# LPDDR2_16bits.net
KiCad netlist of a schematic drawn in Altium Designer
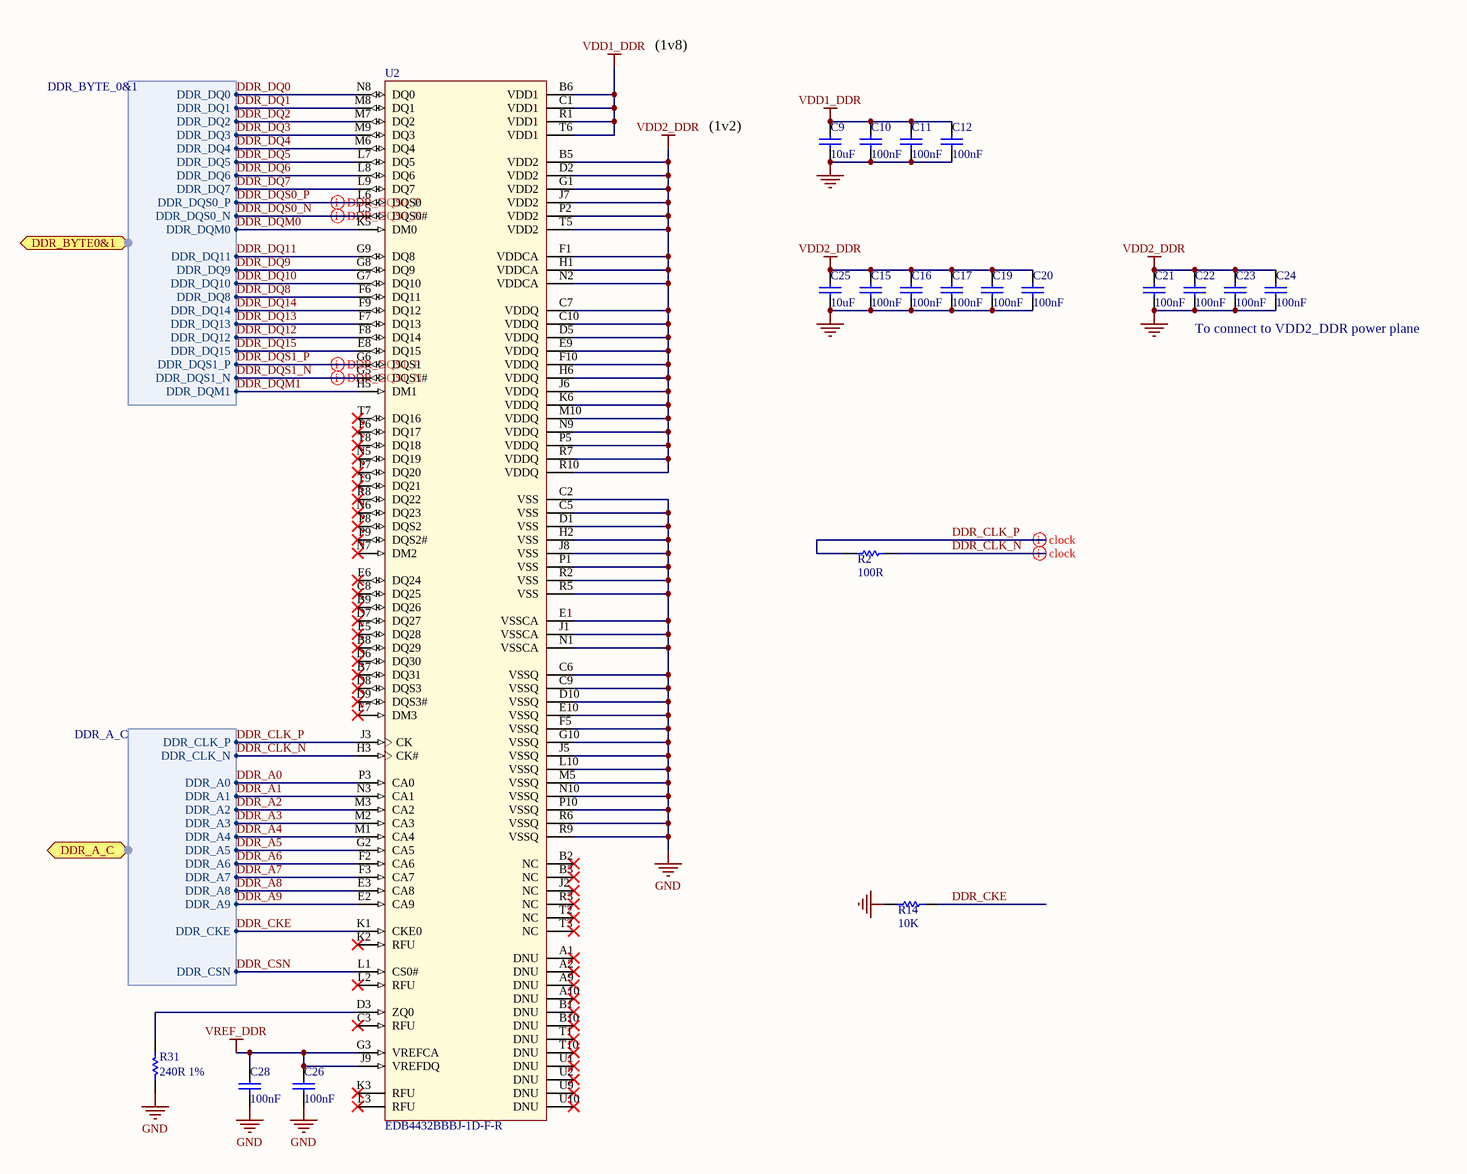
[diagram p0: LPDDR2_16bits .SchDoc]

(export (version "E")
  (design (tool "Eeschema 10.0.6"))
  (components
    (comp (ref "C9")
      (value "10uF")
      (footprint "C0603")
      (description "Capacitor, MLCC, 10uF, 10V, X5R, 10%, 0603, T=0.8mm")
      (fields
        (field (name "INTERNAL_PART_NUMBER") "MCD-01124")
        (field (name "MANUFACTURER_PART_NUMBER") "GRM188R61A106KAAL")
        (field (name "PROVIDED_BY") "SUBCO")
      )
      (libsource (lib "MCD_PARTS_database") (part "Capacitor"))
    )
    (comp (ref "C10")
      (value "100nF")
      (footprint "C0402")
      (description "Capacitor, MLCC, 100nF, 16V, X7R, 10%, 0402, T=0.5mm")
      (fields
        (field (name "INTERNAL_PART_NUMBER") "MCD-00006")
        (field (name "MANUFACTURER_PART_NUMBER") "CC0402KRX7R7BB104")
        (field (name "PROVIDED_BY") "SUBCO")
      )
      (libsource (lib "MCD_PARTS_database") (part "Capacitor"))
    )
    (comp (ref "C11")
      (value "100nF")
      (footprint "C0402")
      (description "Capacitor, MLCC, 100nF, 16V, X7R, 10%, 0402, T=0.5mm")
      (fields
        (field (name "INTERNAL_PART_NUMBER") "MCD-00006")
        (field (name "MANUFACTURER_PART_NUMBER") "CC0402KRX7R7BB104")
        (field (name "PROVIDED_BY") "SUBCO")
      )
      (libsource (lib "MCD_PARTS_database") (part "Capacitor"))
    )
    (comp (ref "C12")
      (value "100nF")
      (footprint "C0402")
      (description "Capacitor, MLCC, 100nF, 16V, X7R, 10%, 0402, T=0.5mm")
      (fields
        (field (name "INTERNAL_PART_NUMBER") "MCD-00006")
        (field (name "MANUFACTURER_PART_NUMBER") "CC0402KRX7R7BB104")
        (field (name "PROVIDED_BY") "SUBCO")
      )
      (libsource (lib "MCD_PARTS_database") (part "Capacitor"))
    )
    (comp (ref "C15")
      (value "100nF")
      (footprint "C0402")
      (description "Capacitor, MLCC, 100nF, 16V, X7R, 10%, 0402, T=0.5mm")
      (fields
        (field (name "INTERNAL_PART_NUMBER") "MCD-00006")
        (field (name "MANUFACTURER_PART_NUMBER") "CC0402KRX7R7BB104")
        (field (name "PROVIDED_BY") "SUBCO")
      )
      (libsource (lib "MCD_PARTS_database") (part "Capacitor"))
    )
    (comp (ref "C16")
      (value "100nF")
      (footprint "C0402")
      (description "Capacitor, MLCC, 100nF, 16V, X7R, 10%, 0402, T=0.5mm")
      (fields
        (field (name "INTERNAL_PART_NUMBER") "MCD-00006")
        (field (name "MANUFACTURER_PART_NUMBER") "CC0402KRX7R7BB104")
        (field (name "PROVIDED_BY") "SUBCO")
      )
      (libsource (lib "MCD_PARTS_database") (part "Capacitor"))
    )
    (comp (ref "C17")
      (value "100nF")
      (footprint "C0402")
      (description "Capacitor, MLCC, 100nF, 16V, X7R, 10%, 0402, T=0.5mm")
      (fields
        (field (name "INTERNAL_PART_NUMBER") "MCD-00006")
        (field (name "MANUFACTURER_PART_NUMBER") "CC0402KRX7R7BB104")
        (field (name "PROVIDED_BY") "SUBCO")
      )
      (libsource (lib "MCD_PARTS_database") (part "Capacitor"))
    )
    (comp (ref "C19")
      (value "100nF")
      (footprint "C0402")
      (description "Capacitor, MLCC, 100nF, 16V, X7R, 10%, 0402, T=0.5mm")
      (fields
        (field (name "INTERNAL_PART_NUMBER") "MCD-00006")
        (field (name "MANUFACTURER_PART_NUMBER") "CC0402KRX7R7BB104")
        (field (name "PROVIDED_BY") "SUBCO")
      )
      (libsource (lib "MCD_PARTS_database") (part "Capacitor"))
    )
    (comp (ref "C20")
      (value "100nF")
      (footprint "C0402")
      (description "Capacitor, MLCC, 100nF, 16V, X7R, 10%, 0402, T=0.5mm")
      (fields
        (field (name "INTERNAL_PART_NUMBER") "MCD-00006")
        (field (name "MANUFACTURER_PART_NUMBER") "CC0402KRX7R7BB104")
        (field (name "PROVIDED_BY") "SUBCO")
      )
      (libsource (lib "MCD_PARTS_database") (part "Capacitor"))
    )
    (comp (ref "C21")
      (value "100nF")
      (footprint "C0402")
      (description "Capacitor, MLCC, 100nF, 16V, X7R, 10%, 0402, T=0.5mm")
      (fields
        (field (name "INTERNAL_PART_NUMBER") "MCD-00006")
        (field (name "MANUFACTURER_PART_NUMBER") "CC0402KRX7R7BB104")
        (field (name "PROVIDED_BY") "SUBCO")
      )
      (libsource (lib "MCD_PARTS_database") (part "Capacitor"))
    )
    (comp (ref "C22")
      (value "100nF")
      (footprint "C0402")
      (description "Capacitor, MLCC, 100nF, 16V, X7R, 10%, 0402, T=0.5mm")
      (fields
        (field (name "INTERNAL_PART_NUMBER") "MCD-00006")
        (field (name "MANUFACTURER_PART_NUMBER") "CC0402KRX7R7BB104")
        (field (name "PROVIDED_BY") "SUBCO")
      )
      (libsource (lib "MCD_PARTS_database") (part "Capacitor"))
    )
    (comp (ref "C23")
      (value "100nF")
      (footprint "C0402")
      (description "Capacitor, MLCC, 100nF, 16V, X7R, 10%, 0402, T=0.5mm")
      (fields
        (field (name "INTERNAL_PART_NUMBER") "MCD-00006")
        (field (name "MANUFACTURER_PART_NUMBER") "CC0402KRX7R7BB104")
        (field (name "PROVIDED_BY") "SUBCO")
      )
      (libsource (lib "MCD_PARTS_database") (part "Capacitor"))
    )
    (comp (ref "C24")
      (value "100nF")
      (footprint "C0402")
      (description "Capacitor, MLCC, 100nF, 16V, X7R, 10%, 0402, T=0.5mm")
      (fields
        (field (name "INTERNAL_PART_NUMBER") "MCD-00006")
        (field (name "MANUFACTURER_PART_NUMBER") "CC0402KRX7R7BB104")
        (field (name "PROVIDED_BY") "SUBCO")
      )
      (libsource (lib "MCD_PARTS_database") (part "Capacitor"))
    )
    (comp (ref "C25")
      (value "10uF")
      (footprint "C0603")
      (description "Capacitor, MLCC, 10uF, 10V, X5R, 10%, 0603, T=0.8mm")
      (fields
        (field (name "INTERNAL_PART_NUMBER") "MCD-01124")
        (field (name "MANUFACTURER_PART_NUMBER") "GRM188R61A106KAAL")
        (field (name "PROVIDED_BY") "SUBCO")
      )
      (libsource (lib "MCD_PARTS_database") (part "Capacitor"))
    )
    (comp (ref "C26")
      (value "100nF")
      (footprint "C0402")
      (description "Capacitor, MLCC, 100nF, 16V, X7R, 10%, 0402, T=0.5mm")
      (fields
        (field (name "INTERNAL_PART_NUMBER") "MCD-00006")
        (field (name "MANUFACTURER_PART_NUMBER") "CC0402KRX7R7BB104")
        (field (name "PROVIDED_BY") "SUBCO")
      )
      (libsource (lib "MCD_PARTS_database") (part "Capacitor"))
    )
    (comp (ref "C28")
      (value "100nF")
      (footprint "C0402")
      (description "Capacitor, MLCC, 100nF, 16V, X7R, 10%, 0402, T=0.5mm")
      (fields
        (field (name "INTERNAL_PART_NUMBER") "MCD-00006")
        (field (name "MANUFACTURER_PART_NUMBER") "CC0402KRX7R7BB104")
        (field (name "PROVIDED_BY") "SUBCO")
      )
      (libsource (lib "MCD_PARTS_database") (part "Capacitor"))
    )
    (comp (ref "R2")
      (value "100R")
      (footprint "R0402")
      (description "Resistor,100R,0402,1%,1/16W")
      (fields
        (field (name "INTERNAL_PART_NUMBER") "MCD-00067")
        (field (name "MANUFACTURER_PART_NUMBER") "RC0402FR-07100RL")
        (field (name "PROVIDED_BY") "SUBCO")
      )
      (libsource (lib "MCD_PARTS_database") (part "Resistor"))
    )
    (comp (ref "R14")
      (value "10K")
      (footprint "R0402")
      (description "Resistor,10K,0402,1%,1/16W")
      (fields
        (field (name "INTERNAL_PART_NUMBER") "MCD-00053")
        (field (name "MANUFACTURER_PART_NUMBER") "RC0402FR-0710KL")
        (field (name "PROVIDED_BY") "SUBCO")
      )
      (libsource (lib "MCD_PARTS_database") (part "Resistor"))
    )
    (comp (ref "R31")
      (value "240R 1%")
      (footprint "R0402")
      (description "Resistor,240R,0402,1%,1/16W")
      (fields
        (field (name "INTERNAL_PART_NUMBER") "MCD-00120")
        (field (name "MANUFACTURER_PART_NUMBER") "RC0402FR-07240RL")
        (field (name "PROVIDED_BY") "SUBCO")
      )
      (libsource (lib "MCD_PARTS_database") (part "Resistor"))
    )
    (comp (ref "U2")
      (value "EDB4432BBBJ-1D-F-R")
      (footprint "ICC_WFBGA134_SDP-SAC302_10X11P5_P065")
      (description "Memory,LPDDR2,4Gb,128Mbx32,533MHz,1066Mb/s,1V8/1V2,FBGA134")
      (fields
        (field (name "INTERNAL_PART_NUMBER") "MCD-01223")
        (field (name "MANUFACTURER") "MICRON")
        (field (name "PROVIDED_BY") "SUBCO")
      )
      (libsource (lib "MCD_PARTS_database") (part "EDB4432BBBJ-1D-F-R"))
    )
  )
  (nets
    (net (code "3") (name "/DDR_A0") (class "Default")
      (node (ref "U2") (pin "P3") (pinfunction "CA0_P3") (pintype "input"))
    )
    (net (code "4") (name "/DDR_A1") (class "Default")
      (node (ref "U2") (pin "N3") (pinfunction "CA1_N3") (pintype "input"))
    )
    (net (code "5") (name "/DDR_A2") (class "Default")
      (node (ref "U2") (pin "M3") (pinfunction "CA2_M3") (pintype "input"))
    )
    (net (code "6") (name "/DDR_A3") (class "Default")
      (node (ref "U2") (pin "M2") (pinfunction "CA3_M2") (pintype "input"))
    )
    (net (code "7") (name "/DDR_A4") (class "Default")
      (node (ref "U2") (pin "M1") (pinfunction "CA4_M1") (pintype "input"))
    )
    (net (code "8") (name "/DDR_A5") (class "Default")
      (node (ref "U2") (pin "G2") (pinfunction "CA5_G2") (pintype "input"))
    )
    (net (code "9") (name "/DDR_A6") (class "Default")
      (node (ref "U2") (pin "F2") (pinfunction "CA6_F2") (pintype "input"))
    )
    (net (code "10") (name "/DDR_A7") (class "Default")
      (node (ref "U2") (pin "F3") (pinfunction "CA7_F3") (pintype "input"))
    )
    (net (code "11") (name "/DDR_A8") (class "Default")
      (node (ref "U2") (pin "E3") (pinfunction "CA8_E3") (pintype "input"))
    )
    (net (code "12") (name "/DDR_A9") (class "Default")
      (node (ref "U2") (pin "E2") (pinfunction "CA9_E2") (pintype "input"))
    )
    (net (code "13") (name "/DDR_CKE") (class "Default")
      (node (ref "R14") (pin "2") (pinfunction "2_2") (pintype "passive"))
      (node (ref "U2") (pin "K1") (pinfunction "CKE0_K1") (pintype "input"))
    )
    (net (code "14") (name "/DDR_CLK_N") (class "Default")
      (node (ref "R2") (pin "2") (pinfunction "2_2") (pintype "passive"))
      (node (ref "U2") (pin "H3") (pinfunction "CK#_H3") (pintype "input"))
    )
    (net (code "15") (name "/DDR_CLK_P") (class "Default")
      (node (ref "R2") (pin "1") (pinfunction "1_1") (pintype "passive"))
      (node (ref "U2") (pin "J3") (pinfunction "CK_J3") (pintype "input"))
    )
    (net (code "16") (name "/DDR_CSN") (class "Default")
      (node (ref "U2") (pin "L1") (pinfunction "CS0#_L1") (pintype "input"))
    )
    (net (code "17") (name "/DDR_DQ0") (class "Default")
      (node (ref "U2") (pin "N8") (pinfunction "DQ0_N8") (pintype "bidirectional"))
    )
    (net (code "18") (name "/DDR_DQ1") (class "Default")
      (node (ref "U2") (pin "M8") (pinfunction "DQ1_M8") (pintype "bidirectional"))
    )
    (net (code "19") (name "/DDR_DQ2") (class "Default")
      (node (ref "U2") (pin "M7") (pinfunction "DQ2_M7") (pintype "bidirectional"))
    )
    (net (code "20") (name "/DDR_DQ3") (class "Default")
      (node (ref "U2") (pin "M9") (pinfunction "DQ3_M9") (pintype "bidirectional"))
    )
    (net (code "21") (name "/DDR_DQ4") (class "Default")
      (node (ref "U2") (pin "M6") (pinfunction "DQ4_M6") (pintype "bidirectional"))
    )
    (net (code "22") (name "/DDR_DQ5") (class "Default")
      (node (ref "U2") (pin "L7") (pinfunction "DQ5_L7") (pintype "bidirectional"))
    )
    (net (code "23") (name "/DDR_DQ6") (class "Default")
      (node (ref "U2") (pin "L8") (pinfunction "DQ6_L8") (pintype "bidirectional"))
    )
    (net (code "24") (name "/DDR_DQ7") (class "Default")
      (node (ref "U2") (pin "L9") (pinfunction "DQ7_L9") (pintype "bidirectional"))
    )
    (net (code "25") (name "/DDR_DQ8") (class "Default")
      (node (ref "U2") (pin "F6") (pinfunction "DQ11_F6") (pintype "bidirectional"))
    )
    (net (code "26") (name "/DDR_DQ9") (class "Default")
      (node (ref "U2") (pin "G8") (pinfunction "DQ9_G8") (pintype "bidirectional"))
    )
    (net (code "27") (name "/DDR_DQ10") (class "Default")
      (node (ref "U2") (pin "G7") (pinfunction "DQ10_G7") (pintype "bidirectional"))
    )
    (net (code "28") (name "/DDR_DQ11") (class "Default")
      (node (ref "U2") (pin "G9") (pinfunction "DQ8_G9") (pintype "bidirectional"))
    )
    (net (code "29") (name "/DDR_DQ12") (class "Default")
      (node (ref "U2") (pin "F8") (pinfunction "DQ14_F8") (pintype "bidirectional"))
    )
    (net (code "30") (name "/DDR_DQ13") (class "Default")
      (node (ref "U2") (pin "F7") (pinfunction "DQ13_F7") (pintype "bidirectional"))
    )
    (net (code "31") (name "/DDR_DQ14") (class "Default")
      (node (ref "U2") (pin "F9") (pinfunction "DQ12_F9") (pintype "bidirectional"))
    )
    (net (code "32") (name "/DDR_DQ15") (class "Default")
      (node (ref "U2") (pin "E8") (pinfunction "DQ15_E8") (pintype "bidirectional"))
    )
    (net (code "33") (name "/DDR_DQM0") (class "Default")
      (node (ref "U2") (pin "K5") (pinfunction "DM0_K5") (pintype "input"))
    )
    (net (code "34") (name "/DDR_DQM1") (class "Default")
      (node (ref "U2") (pin "H5") (pinfunction "DM1_H5") (pintype "input"))
    )
    (net (code "35") (name "/DDR_DQS0_N") (class "Default")
      (node (ref "U2") (pin "L5") (pinfunction "DQS0#_L5") (pintype "bidirectional"))
    )
    (net (code "36") (name "/DDR_DQS0_P") (class "Default")
      (node (ref "U2") (pin "L6") (pinfunction "DQS0_L6") (pintype "bidirectional"))
    )
    (net (code "37") (name "/DDR_DQS1_N") (class "Default")
      (node (ref "U2") (pin "G5") (pinfunction "DQS1#_G5") (pintype "bidirectional"))
    )
    (net (code "38") (name "/DDR_DQS1_P") (class "Default")
      (node (ref "U2") (pin "G6") (pinfunction "DQS1_G6") (pintype "bidirectional"))
    )
    (net (code "41") (name "GND") (class "Default")
      (node (ref "C10") (pin "2") (pinfunction "2_2") (pintype "passive"))
      (node (ref "C11") (pin "2") (pinfunction "2_2") (pintype "passive"))
      (node (ref "C12") (pin "2") (pinfunction "2_2") (pintype "passive"))
      (node (ref "C15") (pin "2") (pinfunction "2_2") (pintype "passive"))
      (node (ref "C16") (pin "2") (pinfunction "2_2") (pintype "passive"))
      (node (ref "C17") (pin "2") (pinfunction "2_2") (pintype "passive"))
      (node (ref "C19") (pin "2") (pinfunction "2_2") (pintype "passive"))
      (node (ref "C20") (pin "2") (pinfunction "2_2") (pintype "passive"))
      (node (ref "C21") (pin "2") (pinfunction "2_2") (pintype "passive"))
      (node (ref "C22") (pin "2") (pinfunction "2_2") (pintype "passive"))
      (node (ref "C23") (pin "2") (pinfunction "2_2") (pintype "passive"))
      (node (ref "C24") (pin "2") (pinfunction "2_2") (pintype "passive"))
      (node (ref "C25") (pin "1") (pinfunction "1_1") (pintype "passive"))
      (node (ref "C26") (pin "2") (pinfunction "2_2") (pintype "passive"))
      (node (ref "C28") (pin "2") (pinfunction "2_2") (pintype "passive"))
      (node (ref "C9") (pin "1") (pinfunction "1_1") (pintype "passive"))
      (node (ref "R14") (pin "1") (pinfunction "1_1") (pintype "passive"))
      (node (ref "R31") (pin "2") (pinfunction "2_2") (pintype "passive"))
      (node (ref "U2") (pin "C2") (pinfunction "VSS_C2") (pintype "power_in"))
      (node (ref "U2") (pin "C5") (pinfunction "VSS_C5") (pintype "power_in"))
      (node (ref "U2") (pin "C6") (pinfunction "VSSQ_C6") (pintype "power_in"))
      (node (ref "U2") (pin "C9") (pinfunction "VSSQ_C9") (pintype "power_in"))
      (node (ref "U2") (pin "D1") (pinfunction "VSS_D1") (pintype "power_in"))
      (node (ref "U2") (pin "D10") (pinfunction "VSSQ_D10") (pintype "power_in"))
      (node (ref "U2") (pin "E1") (pinfunction "VSSCA_E1") (pintype "power_in"))
      (node (ref "U2") (pin "E10") (pinfunction "VSSQ_E10") (pintype "power_in"))
      (node (ref "U2") (pin "F5") (pinfunction "VSSQ_F5") (pintype "power_in"))
      (node (ref "U2") (pin "G10") (pinfunction "VSSQ_G10") (pintype "power_in"))
      (node (ref "U2") (pin "H2") (pinfunction "VSS_H2") (pintype "power_in"))
      (node (ref "U2") (pin "J1") (pinfunction "VSSCA_J1") (pintype "power_in"))
      (node (ref "U2") (pin "J5") (pinfunction "VSSQ_J5") (pintype "power_in"))
      (node (ref "U2") (pin "J8") (pinfunction "VSS_J8") (pintype "power_in"))
      (node (ref "U2") (pin "L10") (pinfunction "VSSQ_L10") (pintype "power_in"))
      (node (ref "U2") (pin "M5") (pinfunction "VSSQ_M5") (pintype "power_in"))
      (node (ref "U2") (pin "N1") (pinfunction "VSSCA_N1") (pintype "power_in"))
      (node (ref "U2") (pin "N10") (pinfunction "VSSQ_N10") (pintype "power_in"))
      (node (ref "U2") (pin "P1") (pinfunction "VSS_P1") (pintype "power_in"))
      (node (ref "U2") (pin "P10") (pinfunction "VSSQ_P10") (pintype "power_in"))
      (node (ref "U2") (pin "R2") (pinfunction "VSS_R2") (pintype "power_in"))
      (node (ref "U2") (pin "R5") (pinfunction "VSS_R5") (pintype "power_in"))
      (node (ref "U2") (pin "R6") (pinfunction "VSSQ_R6") (pintype "power_in"))
      (node (ref "U2") (pin "R9") (pinfunction "VSSQ_R9") (pintype "power_in"))
    )
    (net (code "42") (name "Net-(U2-ZQ0)") (class "Default")
      (node (ref "R31") (pin "1") (pinfunction "1_1") (pintype "passive"))
      (node (ref "U2") (pin "D3") (pinfunction "ZQ0_D3") (pintype "input"))
    )
    (net (code "43") (name "VDD1_DDR") (class "Default")
      (node (ref "C10") (pin "1") (pinfunction "1_1") (pintype "passive"))
      (node (ref "C11") (pin "1") (pinfunction "1_1") (pintype "passive"))
      (node (ref "C12") (pin "1") (pinfunction "1_1") (pintype "passive"))
      (node (ref "C9") (pin "2") (pinfunction "2_2") (pintype "passive"))
      (node (ref "U2") (pin "B6") (pinfunction "VDD1_B6") (pintype "power_in"))
      (node (ref "U2") (pin "C1") (pinfunction "VDD1_C1") (pintype "power_in"))
      (node (ref "U2") (pin "R1") (pinfunction "VDD1_R1") (pintype "power_in"))
      (node (ref "U2") (pin "T6") (pinfunction "VDD1_T6") (pintype "power_in"))
    )
    (net (code "44") (name "VDD2_DDR") (class "Default")
      (node (ref "C15") (pin "1") (pinfunction "1_1") (pintype "passive"))
      (node (ref "C16") (pin "1") (pinfunction "1_1") (pintype "passive"))
      (node (ref "C17") (pin "1") (pinfunction "1_1") (pintype "passive"))
      (node (ref "C19") (pin "1") (pinfunction "1_1") (pintype "passive"))
      (node (ref "C20") (pin "1") (pinfunction "1_1") (pintype "passive"))
      (node (ref "C21") (pin "1") (pinfunction "1_1") (pintype "passive"))
      (node (ref "C22") (pin "1") (pinfunction "1_1") (pintype "passive"))
      (node (ref "C23") (pin "1") (pinfunction "1_1") (pintype "passive"))
      (node (ref "C24") (pin "1") (pinfunction "1_1") (pintype "passive"))
      (node (ref "C25") (pin "2") (pinfunction "2_2") (pintype "passive"))
      (node (ref "U2") (pin "B5") (pinfunction "VDD2_B5") (pintype "power_in"))
      (node (ref "U2") (pin "C10") (pinfunction "VDDQ_C10") (pintype "power_in"))
      (node (ref "U2") (pin "C7") (pinfunction "VDDQ_C7") (pintype "power_in"))
      (node (ref "U2") (pin "D2") (pinfunction "VDD2_D2") (pintype "power_in"))
      (node (ref "U2") (pin "D5") (pinfunction "VDDQ_D5") (pintype "power_in"))
      (node (ref "U2") (pin "E9") (pinfunction "VDDQ_E9") (pintype "power_in"))
      (node (ref "U2") (pin "F1") (pinfunction "VDDCA_F1") (pintype "power_in"))
      (node (ref "U2") (pin "F10") (pinfunction "VDDQ_F10") (pintype "power_in"))
      (node (ref "U2") (pin "G1") (pinfunction "VDD2_G1") (pintype "power_in"))
      (node (ref "U2") (pin "H1") (pinfunction "VDDCA_H1") (pintype "power_in"))
      (node (ref "U2") (pin "H6") (pinfunction "VDDQ_H6") (pintype "power_in"))
      (node (ref "U2") (pin "J6") (pinfunction "VDDQ_J6") (pintype "power_in"))
      (node (ref "U2") (pin "J7") (pinfunction "VDD2_J7") (pintype "power_in"))
      (node (ref "U2") (pin "K6") (pinfunction "VDDQ_K6") (pintype "power_in"))
      (node (ref "U2") (pin "M10") (pinfunction "VDDQ_M10") (pintype "power_in"))
      (node (ref "U2") (pin "N2") (pinfunction "VDDCA_N2") (pintype "power_in"))
      (node (ref "U2") (pin "N9") (pinfunction "VDDQ_N9") (pintype "power_in"))
      (node (ref "U2") (pin "P2") (pinfunction "VDD2_P2") (pintype "power_in"))
      (node (ref "U2") (pin "P5") (pinfunction "VDDQ_P5") (pintype "power_in"))
      (node (ref "U2") (pin "R10") (pinfunction "VDDQ_R10") (pintype "power_in"))
      (node (ref "U2") (pin "R7") (pinfunction "VDDQ_R7") (pintype "power_in"))
      (node (ref "U2") (pin "T5") (pinfunction "VDD2_T5") (pintype "power_in"))
    )
    (net (code "45") (name "VREF_DDR") (class "Default")
      (node (ref "C26") (pin "1") (pinfunction "1_1") (pintype "passive"))
      (node (ref "C28") (pin "1") (pinfunction "1_1") (pintype "passive"))
      (node (ref "U2") (pin "G3") (pinfunction "VREFCA_G3") (pintype "input"))
      (node (ref "U2") (pin "J9") (pinfunction "VREFDQ_J9") (pintype "input"))
    )
    (net (code "46") (name "unconnected-(U2-DM2-PadN7)") (class "Default")
      (node (ref "U2") (pin "N7") (pinfunction "DM2_N7") (pintype "input+no_connect"))
    )
    (net (code "47") (name "unconnected-(U2-DM3-PadE7)") (class "Default")
      (node (ref "U2") (pin "E7") (pinfunction "DM3_E7") (pintype "input+no_connect"))
    )
    (net (code "48") (name "unconnected-(U2-DNU-PadA1)") (class "Default")
      (node (ref "U2") (pin "A1") (pinfunction "DNU_A1") (pintype "passive+no_connect"))
    )
    (net (code "49") (name "unconnected-(U2-DNU-PadA2)") (class "Default")
      (node (ref "U2") (pin "A2") (pinfunction "DNU_A2") (pintype "passive+no_connect"))
    )
    (net (code "50") (name "unconnected-(U2-DNU-PadA9)") (class "Default")
      (node (ref "U2") (pin "A9") (pinfunction "DNU_A9") (pintype "passive+no_connect"))
    )
    (net (code "51") (name "unconnected-(U2-DNU-PadA10)") (class "Default")
      (node (ref "U2") (pin "A10") (pinfunction "DNU_A10") (pintype "passive+no_connect"))
    )
    (net (code "52") (name "unconnected-(U2-DNU-PadB1)") (class "Default")
      (node (ref "U2") (pin "B1") (pinfunction "DNU_B1") (pintype "passive+no_connect"))
    )
    (net (code "53") (name "unconnected-(U2-DNU-PadB10)") (class "Default")
      (node (ref "U2") (pin "B10") (pinfunction "DNU_B10") (pintype "passive+no_connect"))
    )
    (net (code "54") (name "unconnected-(U2-DNU-PadT1)") (class "Default")
      (node (ref "U2") (pin "T1") (pinfunction "DNU_T1") (pintype "passive+no_connect"))
    )
    (net (code "55") (name "unconnected-(U2-DNU-PadT10)") (class "Default")
      (node (ref "U2") (pin "T10") (pinfunction "DNU_T10") (pintype "passive+no_connect"))
    )
    (net (code "56") (name "unconnected-(U2-DNU-PadU1)") (class "Default")
      (node (ref "U2") (pin "U1") (pinfunction "DNU_U1") (pintype "passive+no_connect"))
    )
    (net (code "57") (name "unconnected-(U2-DNU-PadU2)") (class "Default")
      (node (ref "U2") (pin "U2") (pinfunction "DNU_U2") (pintype "passive+no_connect"))
    )
    (net (code "58") (name "unconnected-(U2-DNU-PadU9)") (class "Default")
      (node (ref "U2") (pin "U9") (pinfunction "DNU_U9") (pintype "passive+no_connect"))
    )
    (net (code "59") (name "unconnected-(U2-DNU-PadU10)") (class "Default")
      (node (ref "U2") (pin "U10") (pinfunction "DNU_U10") (pintype "passive+no_connect"))
    )
    (net (code "60") (name "unconnected-(U2-DQ16-PadT7)") (class "Default")
      (node (ref "U2") (pin "T7") (pinfunction "DQ16_T7") (pintype "bidirectional+no_connect"))
    )
    (net (code "61") (name "unconnected-(U2-DQ17-PadP6)") (class "Default")
      (node (ref "U2") (pin "P6") (pinfunction "DQ17_P6") (pintype "bidirectional+no_connect"))
    )
    (net (code "62") (name "unconnected-(U2-DQ18-PadT8)") (class "Default")
      (node (ref "U2") (pin "T8") (pinfunction "DQ18_T8") (pintype "bidirectional+no_connect"))
    )
    (net (code "63") (name "unconnected-(U2-DQ19-PadN5)") (class "Default")
      (node (ref "U2") (pin "N5") (pinfunction "DQ19_N5") (pintype "bidirectional+no_connect"))
    )
    (net (code "64") (name "unconnected-(U2-DQ20-PadP7)") (class "Default")
      (node (ref "U2") (pin "P7") (pinfunction "DQ20_P7") (pintype "bidirectional+no_connect"))
    )
    (net (code "65") (name "unconnected-(U2-DQ21-PadT9)") (class "Default")
      (node (ref "U2") (pin "T9") (pinfunction "DQ21_T9") (pintype "bidirectional+no_connect"))
    )
    (net (code "66") (name "unconnected-(U2-DQ22-PadR8)") (class "Default")
      (node (ref "U2") (pin "R8") (pinfunction "DQ22_R8") (pintype "bidirectional+no_connect"))
    )
    (net (code "67") (name "unconnected-(U2-DQ23-PadN6)") (class "Default")
      (node (ref "U2") (pin "N6") (pinfunction "DQ23_N6") (pintype "bidirectional+no_connect"))
    )
    (net (code "68") (name "unconnected-(U2-DQ24-PadE6)") (class "Default")
      (node (ref "U2") (pin "E6") (pinfunction "DQ24_E6") (pintype "bidirectional+no_connect"))
    )
    (net (code "69") (name "unconnected-(U2-DQ25-PadC8)") (class "Default")
      (node (ref "U2") (pin "C8") (pinfunction "DQ25_C8") (pintype "bidirectional+no_connect"))
    )
    (net (code "70") (name "unconnected-(U2-DQ26-PadB9)") (class "Default")
      (node (ref "U2") (pin "B9") (pinfunction "DQ26_B9") (pintype "bidirectional+no_connect"))
    )
    (net (code "71") (name "unconnected-(U2-DQ27-PadD7)") (class "Default")
      (node (ref "U2") (pin "D7") (pinfunction "DQ27_D7") (pintype "bidirectional+no_connect"))
    )
    (net (code "72") (name "unconnected-(U2-DQ28-PadE5)") (class "Default")
      (node (ref "U2") (pin "E5") (pinfunction "DQ28_E5") (pintype "bidirectional+no_connect"))
    )
    (net (code "73") (name "unconnected-(U2-DQ29-PadB8)") (class "Default")
      (node (ref "U2") (pin "B8") (pinfunction "DQ29_B8") (pintype "bidirectional+no_connect"))
    )
    (net (code "74") (name "unconnected-(U2-DQ30-PadD6)") (class "Default")
      (node (ref "U2") (pin "D6") (pinfunction "DQ30_D6") (pintype "bidirectional+no_connect"))
    )
    (net (code "75") (name "unconnected-(U2-DQ31-PadB7)") (class "Default")
      (node (ref "U2") (pin "B7") (pinfunction "DQ31_B7") (pintype "bidirectional+no_connect"))
    )
    (net (code "76") (name "unconnected-(U2-DQS2#-PadP9)") (class "Default")
      (node (ref "U2") (pin "P9") (pinfunction "DQS2#_P9") (pintype "bidirectional+no_connect"))
    )
    (net (code "77") (name "unconnected-(U2-DQS2-PadP8)") (class "Default")
      (node (ref "U2") (pin "P8") (pinfunction "DQS2_P8") (pintype "bidirectional+no_connect"))
    )
    (net (code "78") (name "unconnected-(U2-DQS3#-PadD9)") (class "Default")
      (node (ref "U2") (pin "D9") (pinfunction "DQS3#_D9") (pintype "bidirectional+no_connect"))
    )
    (net (code "79") (name "unconnected-(U2-DQS3-PadD8)") (class "Default")
      (node (ref "U2") (pin "D8") (pinfunction "DQS3_D8") (pintype "bidirectional+no_connect"))
    )
    (net (code "80") (name "unconnected-(U2-NC-PadB2)") (class "Default")
      (node (ref "U2") (pin "B2") (pinfunction "NC_B2") (pintype "passive+no_connect"))
    )
    (net (code "81") (name "unconnected-(U2-NC-PadB3)") (class "Default")
      (node (ref "U2") (pin "B3") (pinfunction "NC_B3") (pintype "passive+no_connect"))
    )
    (net (code "82") (name "unconnected-(U2-NC-PadJ2)") (class "Default")
      (node (ref "U2") (pin "J2") (pinfunction "NC_J2") (pintype "passive+no_connect"))
    )
    (net (code "83") (name "unconnected-(U2-NC-PadR3)") (class "Default")
      (node (ref "U2") (pin "R3") (pinfunction "NC_R3") (pintype "passive+no_connect"))
    )
    (net (code "84") (name "unconnected-(U2-NC-PadT2)") (class "Default")
      (node (ref "U2") (pin "T2") (pinfunction "NC_T2") (pintype "passive+no_connect"))
    )
    (net (code "85") (name "unconnected-(U2-NC-PadT3)") (class "Default")
      (node (ref "U2") (pin "T3") (pinfunction "NC_T3") (pintype "passive+no_connect"))
    )
    (net (code "86") (name "unconnected-(U2-RFU-PadC3)") (class "Default")
      (node (ref "U2") (pin "C3") (pinfunction "RFU_C3") (pintype "input+no_connect"))
    )
    (net (code "87") (name "unconnected-(U2-RFU-PadK2)") (class "Default")
      (node (ref "U2") (pin "K2") (pinfunction "RFU_K2") (pintype "input+no_connect"))
    )
    (net (code "88") (name "unconnected-(U2-RFU-PadK3)") (class "Default")
      (node (ref "U2") (pin "K3") (pinfunction "RFU_K3") (pintype "passive+no_connect"))
    )
    (net (code "89") (name "unconnected-(U2-RFU-PadL2)") (class "Default")
      (node (ref "U2") (pin "L2") (pinfunction "RFU_L2") (pintype "input+no_connect"))
    )
    (net (code "90") (name "unconnected-(U2-RFU-PadL3)") (class "Default")
      (node (ref "U2") (pin "L3") (pinfunction "RFU_L3") (pintype "passive+no_connect"))
    )
  )
)
